# ltc2344-16.net
KiCad netlist of a schematic drawn in EAGLE
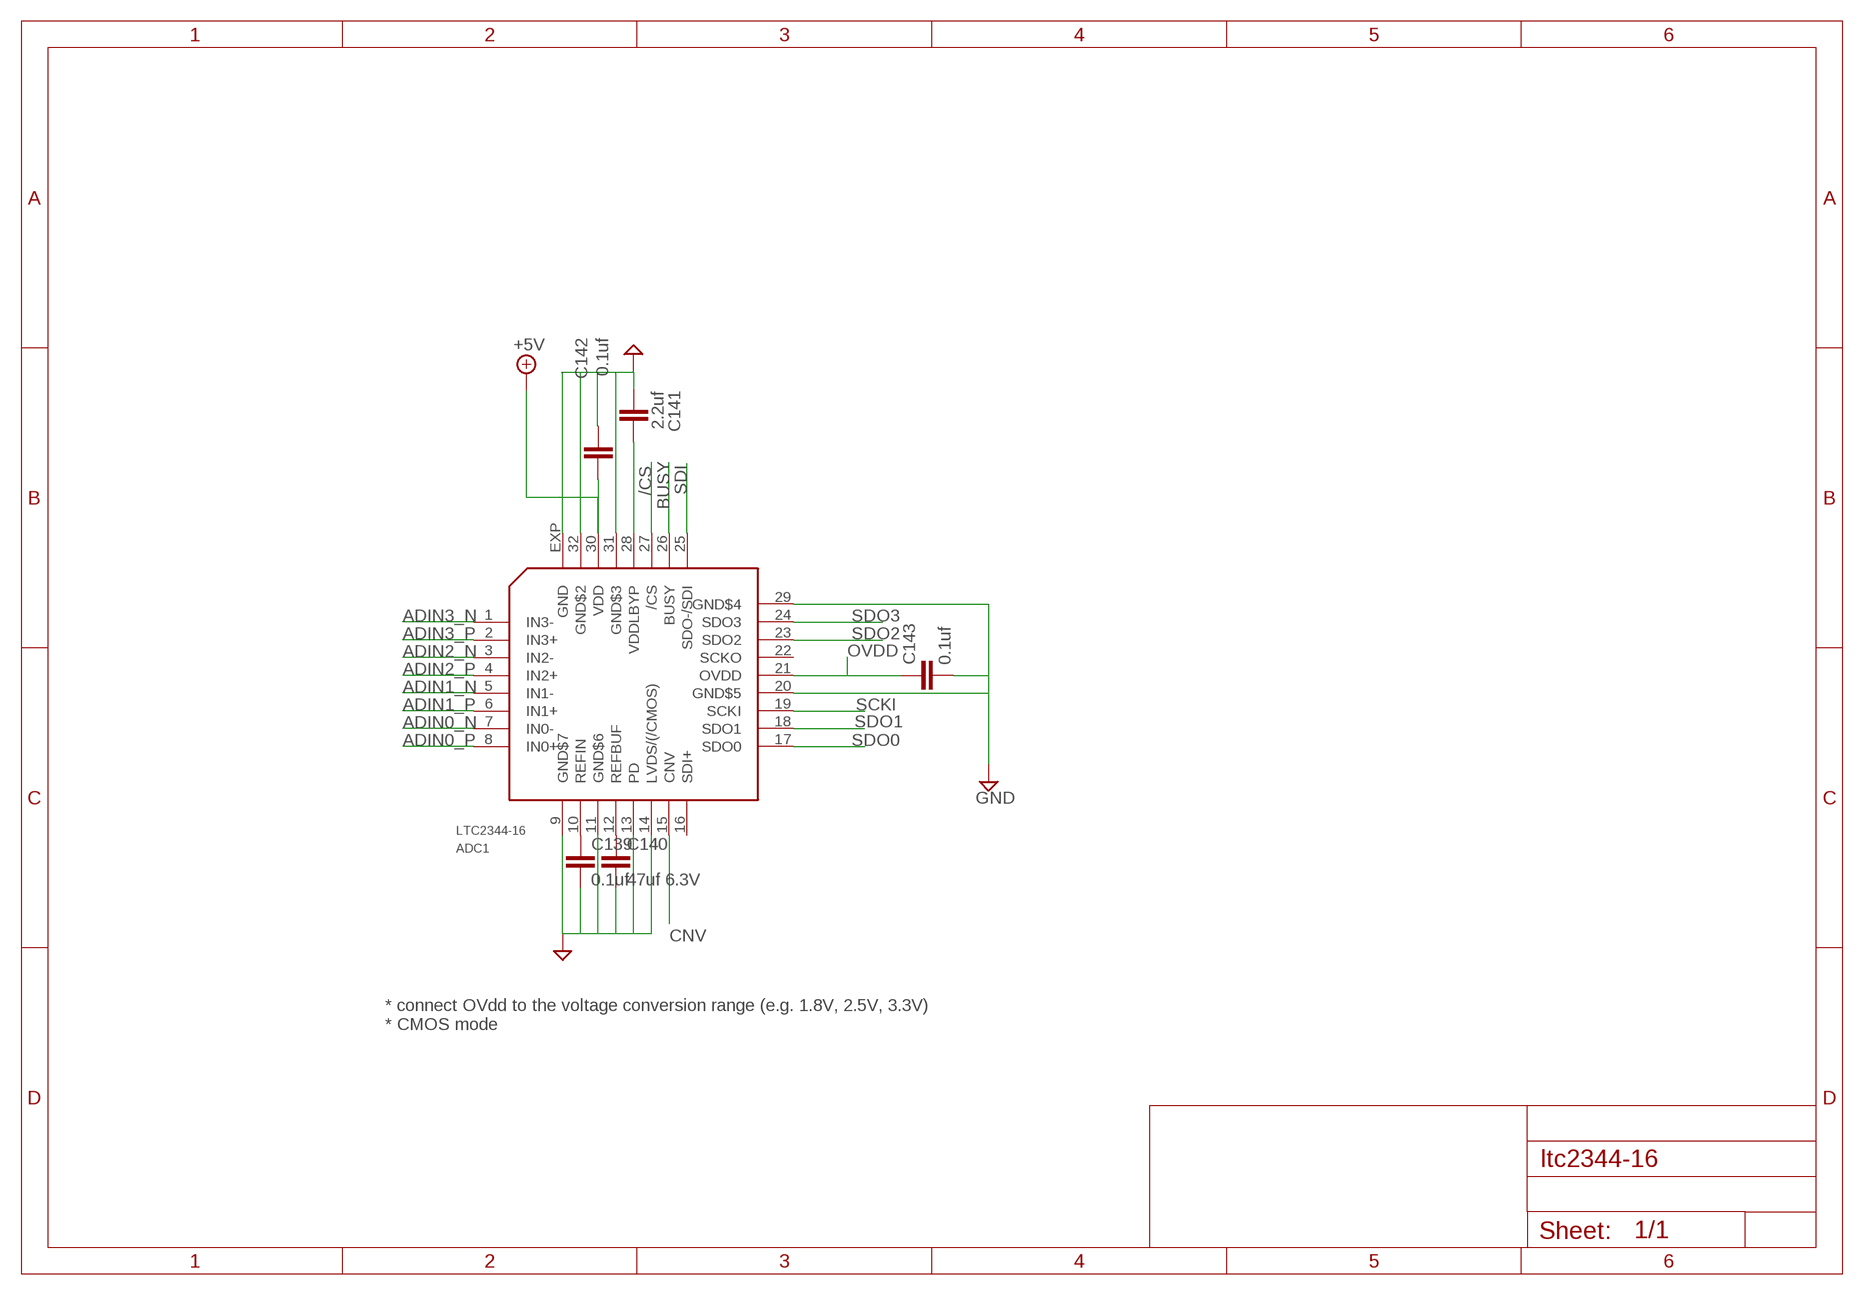
[diagram p0: schematic, sheet 1]

(export (version "E")
  (design (tool "Eeschema 10.0.6"))
  (components
    (comp (ref "ADC1")
      (value "LTC2344-16")
      (footprint "eagle-import:QFN32")
      (libsource (lib "eagle-import") (part "LTC2344-16"))
    )
    (comp (ref "C139")
      (value "0.1uf")
      (footprint "eagle-import:C0402")
      (libsource (lib "eagle-import") (part "C-EUC0402"))
    )
    (comp (ref "C140")
      (value "47uf 6.3V")
      (footprint "eagle-import:C0603")
      (libsource (lib "eagle-import") (part "C-EUC0603"))
    )
    (comp (ref "C141")
      (value "2.2uf")
      (footprint "eagle-import:C0402")
      (libsource (lib "eagle-import") (part "C-EUC0402"))
    )
    (comp (ref "C142")
      (value "0.1uf")
      (footprint "eagle-import:C0402")
      (libsource (lib "eagle-import") (part "C-EUC0402"))
    )
    (comp (ref "C143")
      (value "0.1uf")
      (footprint "eagle-import:C0402")
      (libsource (lib "eagle-import") (part "C-EUC0402"))
    )
  )
  (nets
    (net (code "1") (name "+5V") (class "Default")
      (node (ref "ADC1") (pin "30") (pinfunction "VDD_30") (pintype "bidirectional"))
      (node (ref "C142") (pin "1") (pinfunction "1_1") (pintype "passive"))
    )
    (net (code "2") (name "/ADIN0_N") (class "Default")
      (node (ref "ADC1") (pin "7") (pinfunction "IN0-_7") (pintype "bidirectional"))
    )
    (net (code "3") (name "/ADIN0_P") (class "Default")
      (node (ref "ADC1") (pin "8") (pinfunction "IN0+_8") (pintype "bidirectional"))
    )
    (net (code "4") (name "/ADIN1_N") (class "Default")
      (node (ref "ADC1") (pin "5") (pinfunction "IN1-_5") (pintype "bidirectional"))
    )
    (net (code "5") (name "/ADIN1_P") (class "Default")
      (node (ref "ADC1") (pin "6") (pinfunction "IN1+_6") (pintype "bidirectional"))
    )
    (net (code "6") (name "/ADIN2_N") (class "Default")
      (node (ref "ADC1") (pin "3") (pinfunction "IN2-_3") (pintype "bidirectional"))
    )
    (net (code "7") (name "/ADIN2_P") (class "Default")
      (node (ref "ADC1") (pin "4") (pinfunction "IN2+_4") (pintype "bidirectional"))
    )
    (net (code "8") (name "/ADIN3_N") (class "Default")
      (node (ref "ADC1") (pin "1") (pinfunction "IN3-_1") (pintype "bidirectional"))
    )
    (net (code "9") (name "/ADIN3_P") (class "Default")
      (node (ref "ADC1") (pin "2") (pinfunction "IN3+_2") (pintype "bidirectional"))
    )
    (net (code "10") (name "/BUSY") (class "Default")
      (node (ref "ADC1") (pin "26") (pinfunction "BUSY_26") (pintype "bidirectional"))
    )
    (net (code "11") (name "/CNV") (class "Default")
      (node (ref "ADC1") (pin "15") (pinfunction "CNV_15") (pintype "bidirectional"))
    )
    (net (code "13") (name "/SCKI") (class "Default")
      (node (ref "ADC1") (pin "19") (pinfunction "SCKI_19") (pintype "bidirectional"))
    )
    (net (code "14") (name "/SDI") (class "Default")
      (node (ref "ADC1") (pin "25") (pinfunction "SDO-/SDI_25") (pintype "bidirectional"))
    )
    (net (code "15") (name "/SDO0") (class "Default")
      (node (ref "ADC1") (pin "17") (pinfunction "SDO0_17") (pintype "bidirectional"))
    )
    (net (code "16") (name "/SDO1") (class "Default")
      (node (ref "ADC1") (pin "18") (pinfunction "SDO1_18") (pintype "bidirectional"))
    )
    (net (code "17") (name "/SDO2") (class "Default")
      (node (ref "ADC1") (pin "23") (pinfunction "SDO2_23") (pintype "bidirectional"))
    )
    (net (code "18") (name "/SDO3") (class "Default")
      (node (ref "ADC1") (pin "24") (pinfunction "SDO3_24") (pintype "bidirectional"))
    )
    (net (code "19") (name "/{slash}CS") (class "Default")
      (node (ref "ADC1") (pin "27") (pinfunction "/CS_27") (pintype "bidirectional"))
    )
    (net (code "20") (name "GND") (class "Default")
      (node (ref "ADC1") (pin "11") (pinfunction "GND$6_11") (pintype "bidirectional"))
      (node (ref "ADC1") (pin "13") (pinfunction "PD_13") (pintype "bidirectional"))
      (node (ref "ADC1") (pin "14") (pinfunction "LVDS/(/CMOS)_14") (pintype "bidirectional"))
      (node (ref "ADC1") (pin "20") (pinfunction "GND$5_20") (pintype "bidirectional"))
      (node (ref "ADC1") (pin "29") (pinfunction "GND$4_29") (pintype "bidirectional"))
      (node (ref "ADC1") (pin "31") (pinfunction "GND$3_31") (pintype "bidirectional"))
      (node (ref "ADC1") (pin "32") (pinfunction "GND$2_32") (pintype "bidirectional"))
      (node (ref "ADC1") (pin "9") (pinfunction "GND$7_9") (pintype "bidirectional"))
      (node (ref "ADC1") (pin "EXP") (pinfunction "GND_EXP") (pintype "bidirectional"))
      (node (ref "C139") (pin "2") (pinfunction "2_2") (pintype "passive"))
      (node (ref "C140") (pin "2") (pinfunction "2_2") (pintype "passive"))
      (node (ref "C141") (pin "2") (pinfunction "2_2") (pintype "passive"))
      (node (ref "C142") (pin "2") (pinfunction "2_2") (pintype "passive"))
      (node (ref "C143") (pin "2") (pinfunction "2_2") (pintype "passive"))
    )
    (net (code "21") (name "Net-(ADC1-OVDD)") (class "Default")
      (node (ref "ADC1") (pin "21") (pinfunction "OVDD_21") (pintype "bidirectional"))
      (node (ref "C143") (pin "1") (pinfunction "1_1") (pintype "passive"))
    )
    (net (code "22") (name "Net-(ADC1-REFBUF)") (class "Default")
      (node (ref "ADC1") (pin "12") (pinfunction "REFBUF_12") (pintype "bidirectional"))
      (node (ref "C140") (pin "1") (pinfunction "1_1") (pintype "passive"))
    )
    (net (code "23") (name "Net-(ADC1-REFIN)") (class "Default")
      (node (ref "ADC1") (pin "10") (pinfunction "REFIN_10") (pintype "bidirectional"))
      (node (ref "C139") (pin "1") (pinfunction "1_1") (pintype "passive"))
    )
    (net (code "24") (name "Net-(ADC1-VDDLBYP)") (class "Default")
      (node (ref "ADC1") (pin "28") (pinfunction "VDDLBYP_28") (pintype "bidirectional"))
      (node (ref "C141") (pin "1") (pinfunction "1_1") (pintype "passive"))
    )
    (net (code "25") (name "unconnected-(ADC1-SCKO-Pad22)") (class "Default")
      (node (ref "ADC1") (pin "22") (pinfunction "SCKO_22") (pintype "bidirectional"))
    )
    (net (code "26") (name "unconnected-(ADC1-SDI+-Pad16)") (class "Default")
      (node (ref "ADC1") (pin "16") (pinfunction "SDI+_16") (pintype "bidirectional"))
    )
  )
)
